# mix_conn.net
KiCad netlist of a schematic drawn in Altium Designer
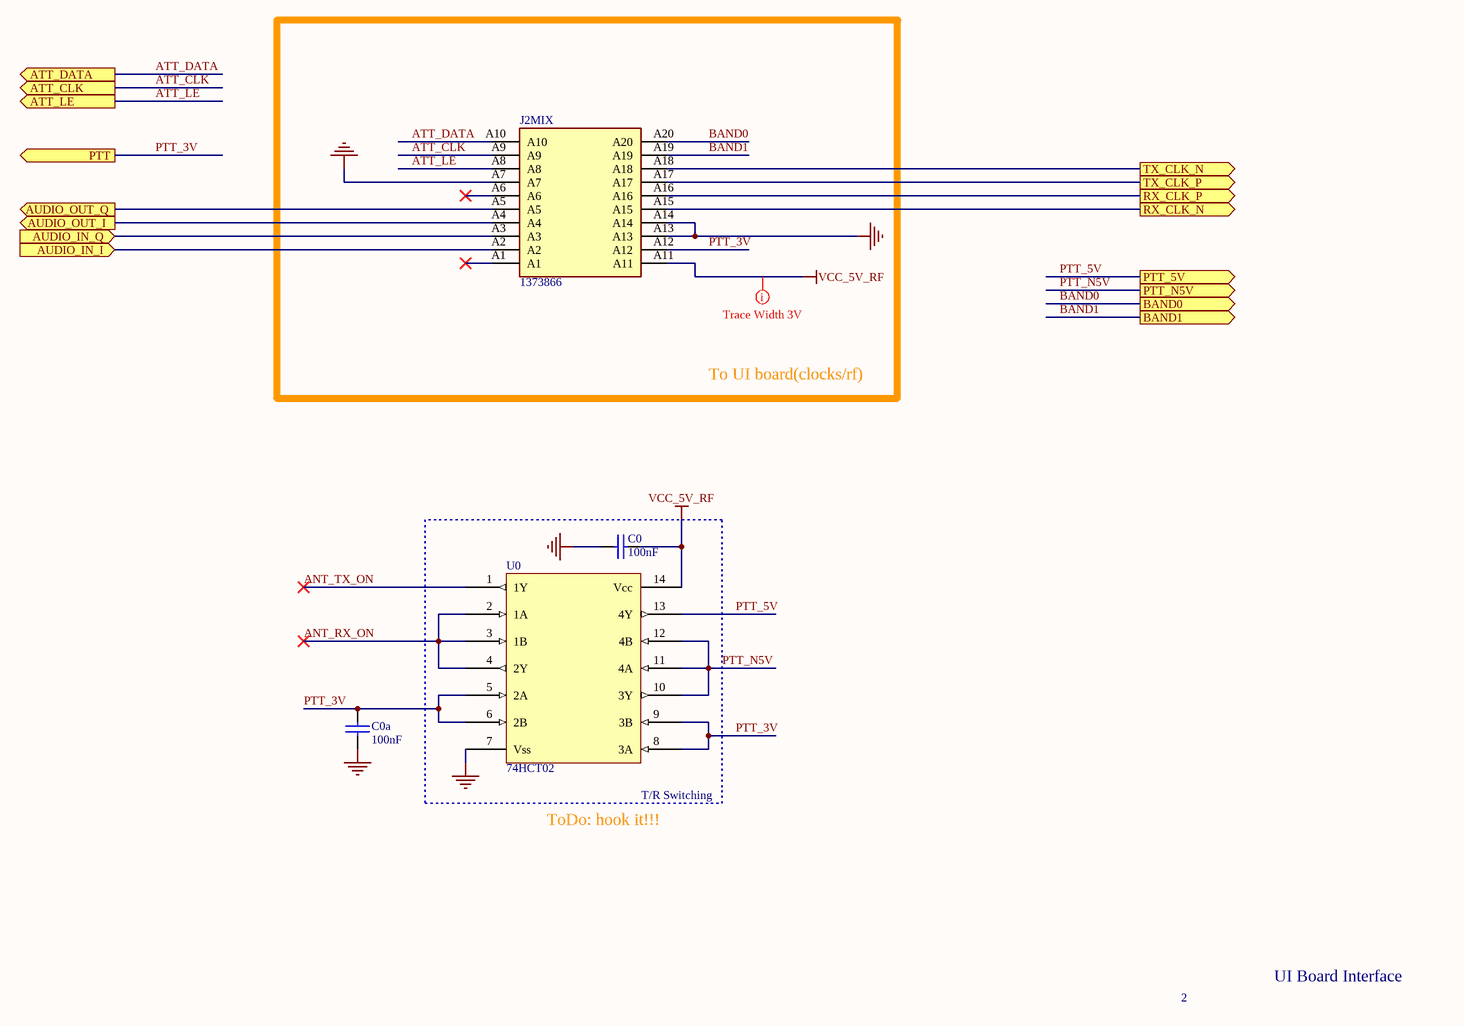
[diagram p0: mix_conn.SchDoc]

(export (version "E")
  (design (tool "Eeschema 10.0.6"))
  (components
    (comp (ref "C0")
      (value "100nF")
      (footprint "0805")
      (description "Capacitor")
      (libsource (lib "mcHF_rf") (part "CAP"))
    )
    (comp (ref "C0a")
      (value "100nF")
      (footprint "0805")
      (description "Capacitor")
      (libsource (lib "mcHF_rf") (part "CAP"))
    )
    (comp (ref "J2MIX")
      (value "1373866")
      (footprint "YuanQi4mm")
      (fields (field (name "MOUSER PART NUMBER") "651-1373866"))
      (libsource (lib "__rf") (part "YQ_20p"))
    )
    (comp (ref "U0")
      (value "74HCT02")
      (footprint "SO-14")
      (description "Quad 2-input NOR gate")
      (libsource (lib "mcHF_rf") (part "74HCT02"))
    )
  )
  (nets
    (net (code "1") (name "/ANT_RX_ON") (class "Default")
      (node (ref "U0") (pin "2") (pinfunction "1A_2") (pintype "input"))
      (node (ref "U0") (pin "3") (pinfunction "1B_3") (pintype "input"))
      (node (ref "U0") (pin "4") (pinfunction "2Y_4") (pintype "output"))
    )
    (net (code "2") (name "/ANT_TX_ON") (class "Default")
      (node (ref "U0") (pin "1") (pinfunction "1Y_1") (pintype "output+no_connect"))
    )
    (net (code "3") (name "/ATT_CLK") (class "Default")
      (node (ref "J2MIX") (pin "A9") (pinfunction "A9_A9") (pintype "passive"))
    )
    (net (code "4") (name "/ATT_DATA") (class "Default")
      (node (ref "J2MIX") (pin "A10") (pinfunction "A10_A10") (pintype "passive"))
    )
    (net (code "5") (name "/ATT_LE") (class "Default")
      (node (ref "J2MIX") (pin "A8") (pinfunction "A8_A8") (pintype "passive"))
    )
    (net (code "6") (name "/AUDIO_IN_I") (class "Default")
      (node (ref "J2MIX") (pin "A2") (pinfunction "A2_A2") (pintype "passive"))
    )
    (net (code "7") (name "/AUDIO_IN_Q") (class "Default")
      (node (ref "J2MIX") (pin "A3") (pinfunction "A3_A3") (pintype "passive"))
    )
    (net (code "8") (name "/AUDIO_OUT_I") (class "Default")
      (node (ref "J2MIX") (pin "A4") (pinfunction "A4_A4") (pintype "passive"))
    )
    (net (code "9") (name "/AUDIO_OUT_Q") (class "Default")
      (node (ref "J2MIX") (pin "A5") (pinfunction "A5_A5") (pintype "passive"))
    )
    (net (code "10") (name "/BAND0") (class "Default")
      (node (ref "J2MIX") (pin "A20") (pinfunction "A20_A20") (pintype "passive"))
    )
    (net (code "11") (name "/BAND1") (class "Default")
      (node (ref "J2MIX") (pin "A19") (pinfunction "A19_A19") (pintype "passive"))
    )
    (net (code "12") (name "/PTT_3V") (class "Default")
      (node (ref "C0a") (pin "1") (pinfunction "1_1") (pintype "passive"))
      (node (ref "J2MIX") (pin "A12") (pinfunction "A12_A12") (pintype "passive"))
      (node (ref "U0") (pin "5") (pinfunction "2A_5") (pintype "input"))
      (node (ref "U0") (pin "6") (pinfunction "2B_6") (pintype "input"))
      (node (ref "U0") (pin "8") (pinfunction "3A_8") (pintype "input"))
      (node (ref "U0") (pin "9") (pinfunction "3B_9") (pintype "input"))
    )
    (net (code "13") (name "/PTT_5V") (class "Default")
      (node (ref "U0") (pin "13") (pinfunction "4Y_13") (pintype "output"))
    )
    (net (code "14") (name "/PTT_N5V") (class "Default")
      (node (ref "U0") (pin "10") (pinfunction "3Y_10") (pintype "output"))
      (node (ref "U0") (pin "11") (pinfunction "4A_11") (pintype "input"))
      (node (ref "U0") (pin "12") (pinfunction "4B_12") (pintype "input"))
    )
    (net (code "15") (name "/RX_CLK_N") (class "Default")
      (node (ref "J2MIX") (pin "A15") (pinfunction "A15_A15") (pintype "passive"))
    )
    (net (code "16") (name "/RX_CLK_P") (class "Default")
      (node (ref "J2MIX") (pin "A16") (pinfunction "A16_A16") (pintype "passive"))
    )
    (net (code "17") (name "/TX_CLK_N") (class "Default")
      (node (ref "J2MIX") (pin "A18") (pinfunction "A18_A18") (pintype "passive"))
    )
    (net (code "18") (name "/TX_CLK_P") (class "Default")
      (node (ref "J2MIX") (pin "A17") (pinfunction "A17_A17") (pintype "passive"))
    )
    (net (code "19") (name "GND") (class "Default")
      (node (ref "C0") (pin "2") (pinfunction "2_2") (pintype "passive"))
      (node (ref "C0a") (pin "2") (pinfunction "2_2") (pintype "passive"))
      (node (ref "J2MIX") (pin "A13") (pinfunction "A13_A13") (pintype "passive"))
      (node (ref "J2MIX") (pin "A14") (pinfunction "A14_A14") (pintype "passive"))
      (node (ref "J2MIX") (pin "A7") (pinfunction "A7_A7") (pintype "passive"))
      (node (ref "U0") (pin "7") (pinfunction "Vss_7") (pintype "power_in"))
    )
    (net (code "20") (name "VCC_5V_RF") (class "Default")
      (node (ref "C0") (pin "1") (pinfunction "1_1") (pintype "passive"))
      (node (ref "J2MIX") (pin "A11") (pinfunction "A11_A11") (pintype "passive"))
      (node (ref "U0") (pin "14") (pinfunction "Vcc_14") (pintype "power_in"))
    )
    (net (code "21") (name "unconnected-(J2MIX-PadA1)") (class "Default")
      (node (ref "J2MIX") (pin "A1") (pinfunction "A1_A1") (pintype "passive+no_connect"))
    )
    (net (code "22") (name "unconnected-(J2MIX-PadA6)") (class "Default")
      (node (ref "J2MIX") (pin "A6") (pinfunction "A6_A6") (pintype "passive+no_connect"))
    )
  )
)
